# Keybon_REV_1_1.net
KiCad netlist of a schematic drawn in EAGLE
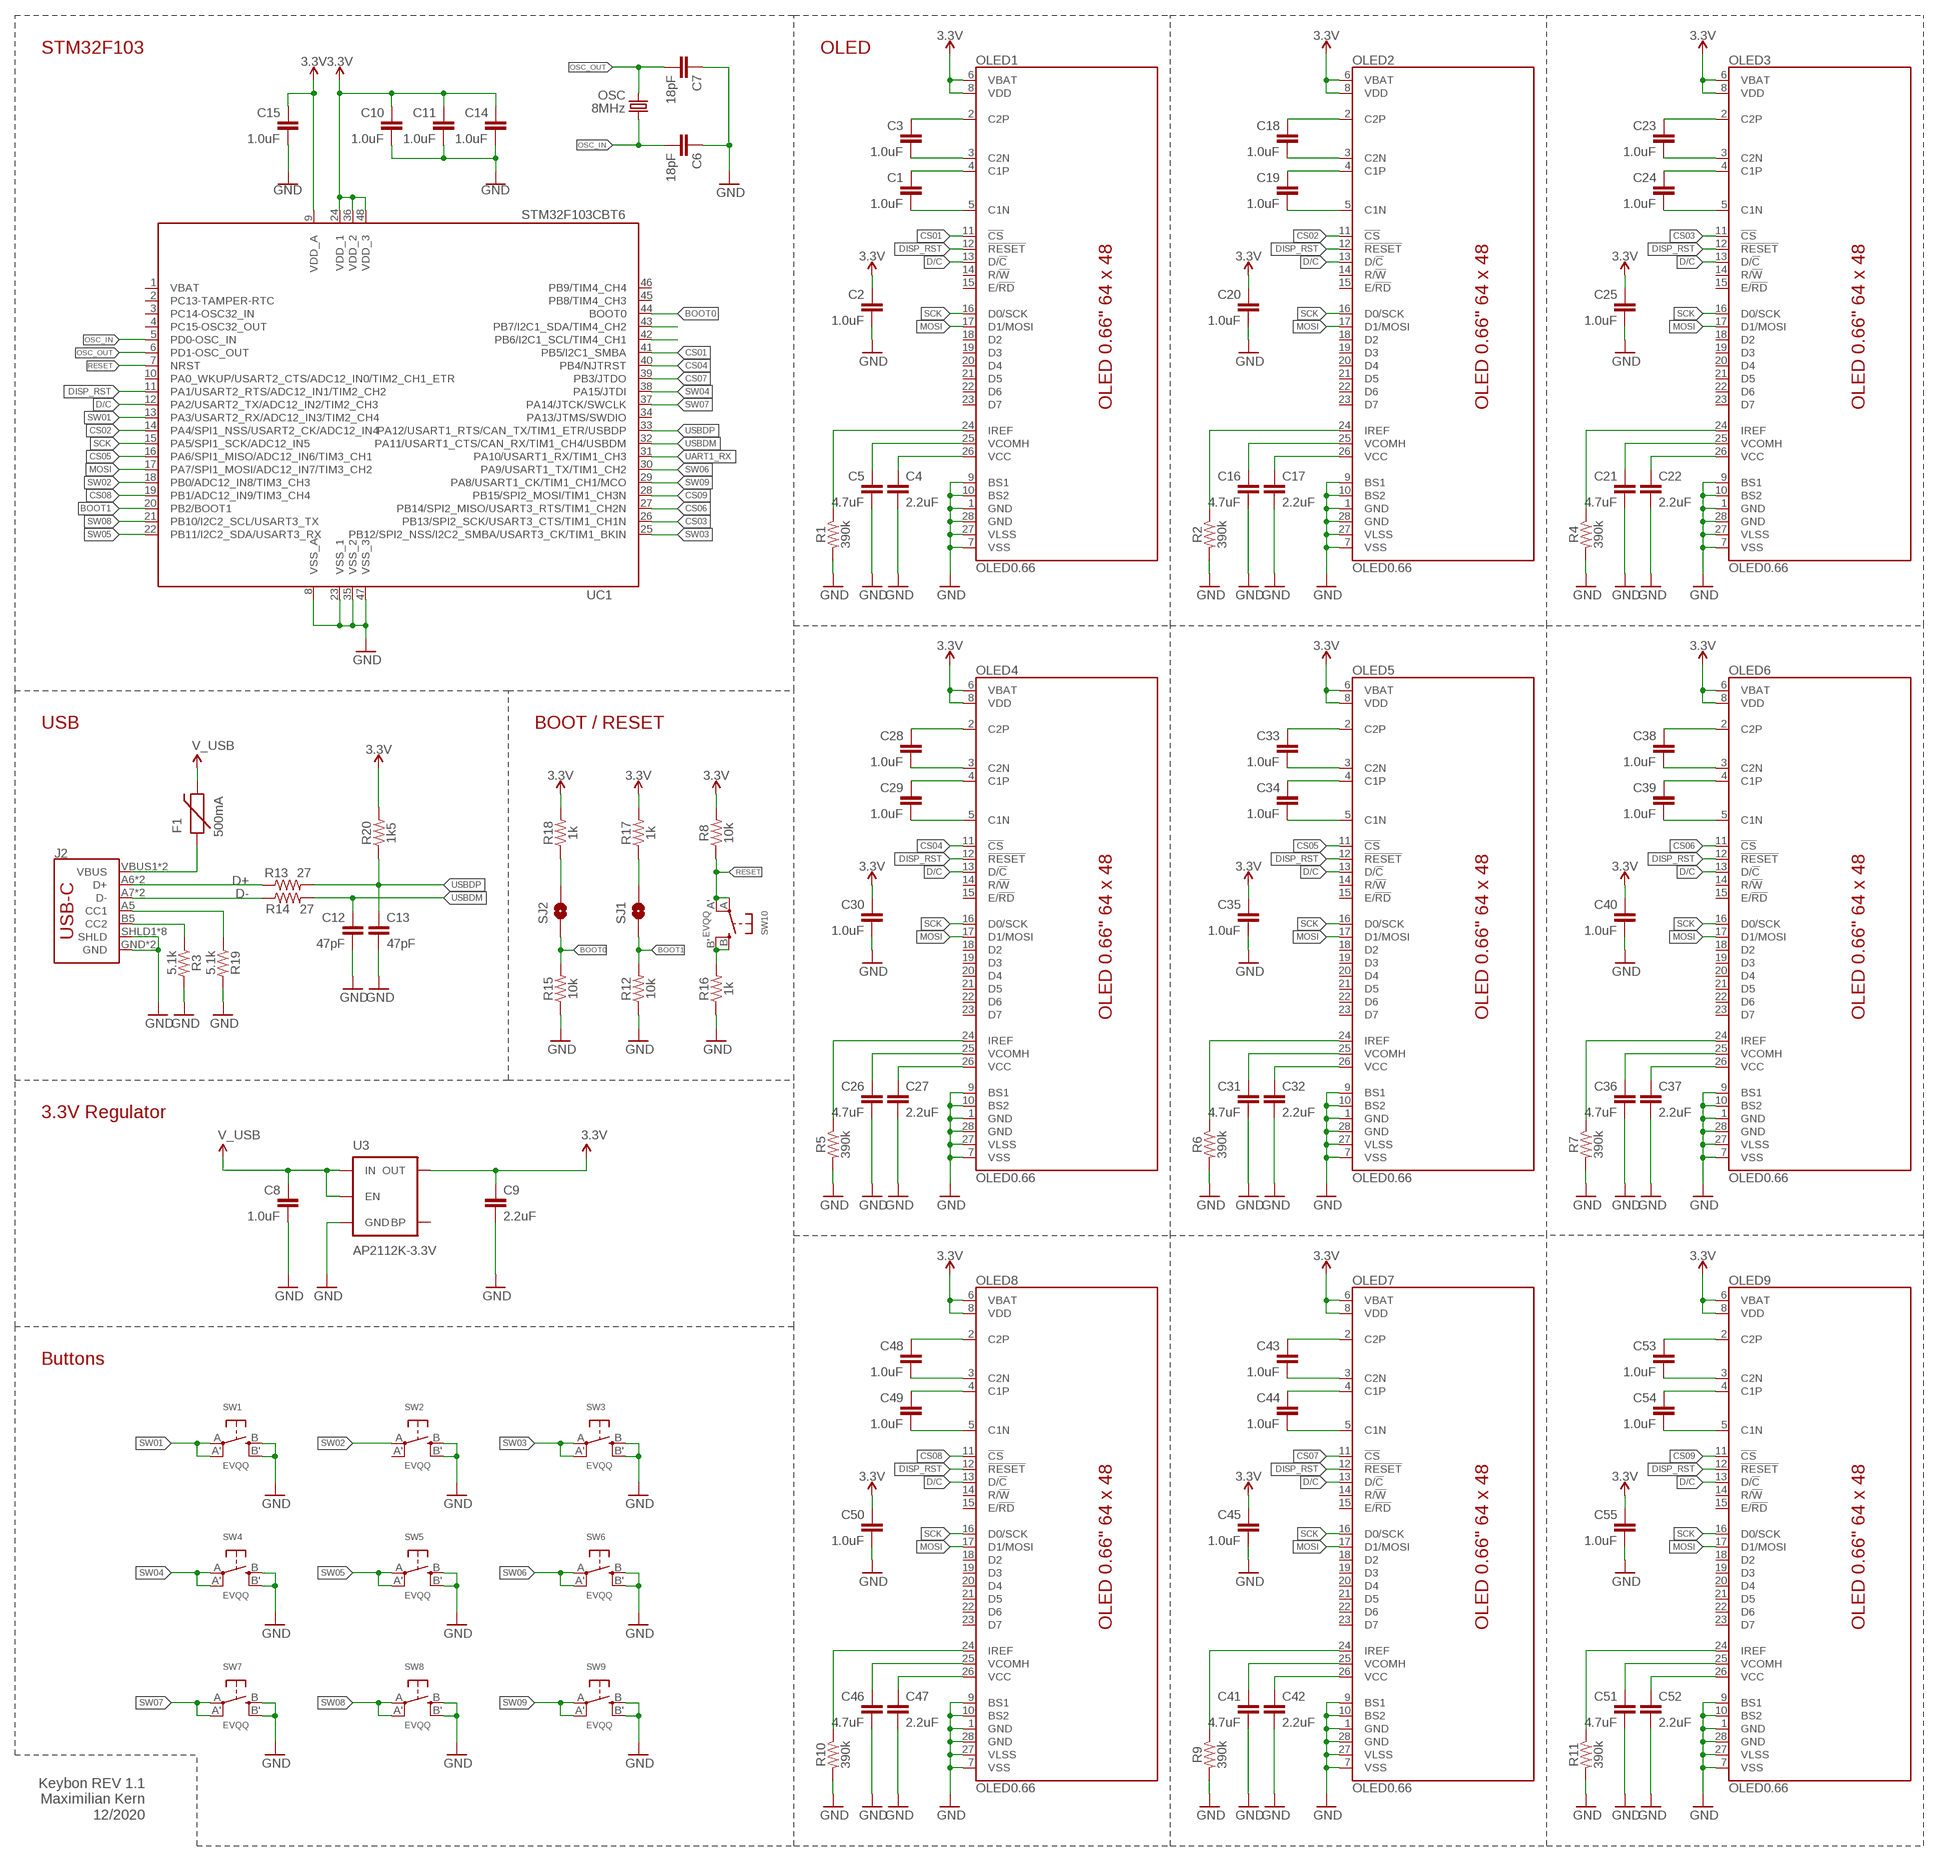
[diagram p0: schematic, sheet 1]

(export (version "E")
  (design (tool "Eeschema 10.0.6"))
  (components
    (comp (ref "C1")
      (value "1.0uF")
      (footprint "eagle-import:0805")
      (libsource (lib "eagle-import") (part "1.0UF-0805-25V-(+80/-20%)"))
    )
    (comp (ref "C2")
      (value "1.0uF")
      (footprint "eagle-import:0805")
      (libsource (lib "eagle-import") (part "1.0UF-0805-25V-(+80/-20%)"))
    )
    (comp (ref "C3")
      (value "1.0uF")
      (footprint "eagle-import:0805")
      (libsource (lib "eagle-import") (part "1.0UF-0805-25V-(+80/-20%)"))
    )
    (comp (ref "C4")
      (value "2.2uF")
      (footprint "eagle-import:0805")
      (libsource (lib "eagle-import") (part "1.0UF-0805-25V-(+80/-20%)"))
    )
    (comp (ref "C5")
      (value "4.7uF")
      (footprint "eagle-import:0603")
      (libsource (lib "eagle-import") (part "4.7UF0603"))
    )
    (comp (ref "C6")
      (value "18pF")
      (footprint "eagle-import:0603")
      (libsource (lib "eagle-import") (part "47PF-0603-50V-5%"))
    )
    (comp (ref "C7")
      (value "18pF")
      (footprint "eagle-import:0603")
      (libsource (lib "eagle-import") (part "47PF-0603-50V-5%"))
    )
    (comp (ref "C8")
      (value "1.0uF")
      (footprint "eagle-import:0805")
      (libsource (lib "eagle-import") (part "1.0UF-0805-25V-(+80/-20%)"))
    )
    (comp (ref "C9")
      (value "2.2uF")
      (footprint "eagle-import:0805")
      (libsource (lib "eagle-import") (part "1.0UF-0805-25V-(+80/-20%)"))
    )
    (comp (ref "C10")
      (value "1.0uF")
      (footprint "eagle-import:0805")
      (libsource (lib "eagle-import") (part "1.0UF-0805-25V-(+80/-20%)"))
    )
    (comp (ref "C11")
      (value "1.0uF")
      (footprint "eagle-import:0805")
      (libsource (lib "eagle-import") (part "1.0UF-0805-25V-(+80/-20%)"))
    )
    (comp (ref "C12")
      (value "47pF")
      (footprint "eagle-import:0603")
      (libsource (lib "eagle-import") (part "47PF-0603-50V-5%"))
    )
    (comp (ref "C13")
      (value "47pF")
      (footprint "eagle-import:0603")
      (libsource (lib "eagle-import") (part "47PF-0603-50V-5%"))
    )
    (comp (ref "C14")
      (value "1.0uF")
      (footprint "eagle-import:0805")
      (libsource (lib "eagle-import") (part "1.0UF-0805-25V-(+80/-20%)"))
    )
    (comp (ref "C15")
      (value "1.0uF")
      (footprint "eagle-import:0805")
      (libsource (lib "eagle-import") (part "1.0UF-0805-25V-(+80/-20%)"))
    )
    (comp (ref "C16")
      (value "4.7uF")
      (footprint "eagle-import:0603")
      (libsource (lib "eagle-import") (part "4.7UF0603"))
    )
    (comp (ref "C17")
      (value "2.2uF")
      (footprint "eagle-import:0805")
      (libsource (lib "eagle-import") (part "1.0UF-0805-25V-(+80/-20%)"))
    )
    (comp (ref "C18")
      (value "1.0uF")
      (footprint "eagle-import:0805")
      (libsource (lib "eagle-import") (part "1.0UF-0805-25V-(+80/-20%)"))
    )
    (comp (ref "C19")
      (value "1.0uF")
      (footprint "eagle-import:0805")
      (libsource (lib "eagle-import") (part "1.0UF-0805-25V-(+80/-20%)"))
    )
    (comp (ref "C20")
      (value "1.0uF")
      (footprint "eagle-import:0805")
      (libsource (lib "eagle-import") (part "1.0UF-0805-25V-(+80/-20%)"))
    )
    (comp (ref "C21")
      (value "4.7uF")
      (footprint "eagle-import:0603")
      (libsource (lib "eagle-import") (part "4.7UF0603"))
    )
    (comp (ref "C22")
      (value "2.2uF")
      (footprint "eagle-import:0805")
      (libsource (lib "eagle-import") (part "1.0UF-0805-25V-(+80/-20%)"))
    )
    (comp (ref "C23")
      (value "1.0uF")
      (footprint "eagle-import:0805")
      (libsource (lib "eagle-import") (part "1.0UF-0805-25V-(+80/-20%)"))
    )
    (comp (ref "C24")
      (value "1.0uF")
      (footprint "eagle-import:0805")
      (libsource (lib "eagle-import") (part "1.0UF-0805-25V-(+80/-20%)"))
    )
    (comp (ref "C25")
      (value "1.0uF")
      (footprint "eagle-import:0805")
      (libsource (lib "eagle-import") (part "1.0UF-0805-25V-(+80/-20%)"))
    )
    (comp (ref "C26")
      (value "4.7uF")
      (footprint "eagle-import:0603")
      (libsource (lib "eagle-import") (part "4.7UF0603"))
    )
    (comp (ref "C27")
      (value "2.2uF")
      (footprint "eagle-import:0805")
      (libsource (lib "eagle-import") (part "1.0UF-0805-25V-(+80/-20%)"))
    )
    (comp (ref "C28")
      (value "1.0uF")
      (footprint "eagle-import:0805")
      (libsource (lib "eagle-import") (part "1.0UF-0805-25V-(+80/-20%)"))
    )
    (comp (ref "C29")
      (value "1.0uF")
      (footprint "eagle-import:0805")
      (libsource (lib "eagle-import") (part "1.0UF-0805-25V-(+80/-20%)"))
    )
    (comp (ref "C30")
      (value "1.0uF")
      (footprint "eagle-import:0805")
      (libsource (lib "eagle-import") (part "1.0UF-0805-25V-(+80/-20%)"))
    )
    (comp (ref "C31")
      (value "4.7uF")
      (footprint "eagle-import:0603")
      (libsource (lib "eagle-import") (part "4.7UF0603"))
    )
    (comp (ref "C32")
      (value "2.2uF")
      (footprint "eagle-import:0805")
      (libsource (lib "eagle-import") (part "1.0UF-0805-25V-(+80/-20%)"))
    )
    (comp (ref "C33")
      (value "1.0uF")
      (footprint "eagle-import:0805")
      (libsource (lib "eagle-import") (part "1.0UF-0805-25V-(+80/-20%)"))
    )
    (comp (ref "C34")
      (value "1.0uF")
      (footprint "eagle-import:0805")
      (libsource (lib "eagle-import") (part "1.0UF-0805-25V-(+80/-20%)"))
    )
    (comp (ref "C35")
      (value "1.0uF")
      (footprint "eagle-import:0805")
      (libsource (lib "eagle-import") (part "1.0UF-0805-25V-(+80/-20%)"))
    )
    (comp (ref "C36")
      (value "4.7uF")
      (footprint "eagle-import:0603")
      (libsource (lib "eagle-import") (part "4.7UF0603"))
    )
    (comp (ref "C37")
      (value "2.2uF")
      (footprint "eagle-import:0805")
      (libsource (lib "eagle-import") (part "1.0UF-0805-25V-(+80/-20%)"))
    )
    (comp (ref "C38")
      (value "1.0uF")
      (footprint "eagle-import:0805")
      (libsource (lib "eagle-import") (part "1.0UF-0805-25V-(+80/-20%)"))
    )
    (comp (ref "C39")
      (value "1.0uF")
      (footprint "eagle-import:0805")
      (libsource (lib "eagle-import") (part "1.0UF-0805-25V-(+80/-20%)"))
    )
    (comp (ref "C40")
      (value "1.0uF")
      (footprint "eagle-import:0805")
      (libsource (lib "eagle-import") (part "1.0UF-0805-25V-(+80/-20%)"))
    )
    (comp (ref "C41")
      (value "4.7uF")
      (footprint "eagle-import:0603")
      (libsource (lib "eagle-import") (part "4.7UF0603"))
    )
    (comp (ref "C42")
      (value "2.2uF")
      (footprint "eagle-import:0805")
      (libsource (lib "eagle-import") (part "1.0UF-0805-25V-(+80/-20%)"))
    )
    (comp (ref "C43")
      (value "1.0uF")
      (footprint "eagle-import:0805")
      (libsource (lib "eagle-import") (part "1.0UF-0805-25V-(+80/-20%)"))
    )
    (comp (ref "C44")
      (value "1.0uF")
      (footprint "eagle-import:0805")
      (libsource (lib "eagle-import") (part "1.0UF-0805-25V-(+80/-20%)"))
    )
    (comp (ref "C45")
      (value "1.0uF")
      (footprint "eagle-import:0805")
      (libsource (lib "eagle-import") (part "1.0UF-0805-25V-(+80/-20%)"))
    )
    (comp (ref "C46")
      (value "4.7uF")
      (footprint "eagle-import:0603")
      (libsource (lib "eagle-import") (part "4.7UF0603"))
    )
    (comp (ref "C47")
      (value "2.2uF")
      (footprint "eagle-import:0805")
      (libsource (lib "eagle-import") (part "1.0UF-0805-25V-(+80/-20%)"))
    )
    (comp (ref "C48")
      (value "1.0uF")
      (footprint "eagle-import:0805")
      (libsource (lib "eagle-import") (part "1.0UF-0805-25V-(+80/-20%)"))
    )
    (comp (ref "C49")
      (value "1.0uF")
      (footprint "eagle-import:0805")
      (libsource (lib "eagle-import") (part "1.0UF-0805-25V-(+80/-20%)"))
    )
    (comp (ref "C50")
      (value "1.0uF")
      (footprint "eagle-import:0805")
      (libsource (lib "eagle-import") (part "1.0UF-0805-25V-(+80/-20%)"))
    )
    (comp (ref "C51")
      (value "4.7uF")
      (footprint "eagle-import:0603")
      (libsource (lib "eagle-import") (part "4.7UF0603"))
    )
    (comp (ref "C52")
      (value "2.2uF")
      (footprint "eagle-import:0805")
      (libsource (lib "eagle-import") (part "1.0UF-0805-25V-(+80/-20%)"))
    )
    (comp (ref "C53")
      (value "1.0uF")
      (footprint "eagle-import:0805")
      (libsource (lib "eagle-import") (part "1.0UF-0805-25V-(+80/-20%)"))
    )
    (comp (ref "C54")
      (value "1.0uF")
      (footprint "eagle-import:0805")
      (libsource (lib "eagle-import") (part "1.0UF-0805-25V-(+80/-20%)"))
    )
    (comp (ref "C55")
      (value "1.0uF")
      (footprint "eagle-import:0805")
      (libsource (lib "eagle-import") (part "1.0UF-0805-25V-(+80/-20%)"))
    )
    (comp (ref "F1")
      (value "500mA")
      (footprint "eagle-import:PTC-1206")
      (libsource (lib "eagle-import") (part "PTCSMD"))
    )
    (comp (ref "J2")
      (value "USB_C16PIN")
      (footprint "eagle-import:USB-C-16P")
      (libsource (lib "eagle-import") (part "USB_C16PIN"))
    )
    (comp (ref "OLED1")
      (value "OLED0.66")
      (footprint "eagle-import:OLED-0.66-64X48")
      (libsource (lib "eagle-import") (part "OLED0.66"))
    )
    (comp (ref "OLED2")
      (value "OLED0.66")
      (footprint "eagle-import:OLED-0.66-64X48")
      (libsource (lib "eagle-import") (part "OLED0.66"))
    )
    (comp (ref "OLED3")
      (value "OLED0.66")
      (footprint "eagle-import:OLED-0.66-64X48")
      (libsource (lib "eagle-import") (part "OLED0.66"))
    )
    (comp (ref "OLED4")
      (value "OLED0.66")
      (footprint "eagle-import:OLED-0.66-64X48")
      (libsource (lib "eagle-import") (part "OLED0.66"))
    )
    (comp (ref "OLED5")
      (value "OLED0.66")
      (footprint "eagle-import:OLED-0.66-64X48")
      (libsource (lib "eagle-import") (part "OLED0.66"))
    )
    (comp (ref "OLED6")
      (value "OLED0.66")
      (footprint "eagle-import:OLED-0.66-64X48")
      (libsource (lib "eagle-import") (part "OLED0.66"))
    )
    (comp (ref "OLED7")
      (value "OLED0.66")
      (footprint "eagle-import:OLED-0.66-64X48")
      (libsource (lib "eagle-import") (part "OLED0.66"))
    )
    (comp (ref "OLED8")
      (value "OLED0.66")
      (footprint "eagle-import:OLED-0.66-64X48")
      (libsource (lib "eagle-import") (part "OLED0.66"))
    )
    (comp (ref "OLED9")
      (value "OLED0.66")
      (footprint "eagle-import:OLED-0.66-64X48")
      (libsource (lib "eagle-import") (part "OLED0.66"))
    )
    (comp (ref "OSC")
      (value "8MHz")
      (footprint "eagle-import:CRYSTAL-SMD-5X3")
      (libsource (lib "eagle-import") (part "CRYSTAL5X3"))
    )
    (comp (ref "R1")
      (value "390k")
      (footprint "eagle-import:0603")
      (libsource (lib "eagle-import") (part "10KOHM-0603-1/10W-1%"))
    )
    (comp (ref "R2")
      (value "390k")
      (footprint "eagle-import:0603")
      (libsource (lib "eagle-import") (part "10KOHM-0603-1/10W-1%"))
    )
    (comp (ref "R3")
      (value "5.1k")
      (footprint "eagle-import:0603")
      (libsource (lib "eagle-import") (part "10KOHM-0603-1/10W-1%"))
    )
    (comp (ref "R4")
      (value "390k")
      (footprint "eagle-import:0603")
      (libsource (lib "eagle-import") (part "10KOHM-0603-1/10W-1%"))
    )
    (comp (ref "R5")
      (value "390k")
      (footprint "eagle-import:0603")
      (libsource (lib "eagle-import") (part "10KOHM-0603-1/10W-1%"))
    )
    (comp (ref "R6")
      (value "390k")
      (footprint "eagle-import:0603")
      (libsource (lib "eagle-import") (part "10KOHM-0603-1/10W-1%"))
    )
    (comp (ref "R7")
      (value "390k")
      (footprint "eagle-import:0603")
      (libsource (lib "eagle-import") (part "10KOHM-0603-1/10W-1%"))
    )
    (comp (ref "R8")
      (value "10k")
      (footprint "eagle-import:0603")
      (libsource (lib "eagle-import") (part "10KOHM-0603-1/10W-1%"))
    )
    (comp (ref "R9")
      (value "390k")
      (footprint "eagle-import:0603")
      (libsource (lib "eagle-import") (part "10KOHM-0603-1/10W-1%"))
    )
    (comp (ref "R10")
      (value "390k")
      (footprint "eagle-import:0603")
      (libsource (lib "eagle-import") (part "10KOHM-0603-1/10W-1%"))
    )
    (comp (ref "R11")
      (value "390k")
      (footprint "eagle-import:0603")
      (libsource (lib "eagle-import") (part "10KOHM-0603-1/10W-1%"))
    )
    (comp (ref "R12")
      (value "10k")
      (footprint "eagle-import:0603")
      (libsource (lib "eagle-import") (part "10KOHM-0603-1/10W-1%"))
    )
    (comp (ref "R13")
      (value "27")
      (footprint "eagle-import:0603")
      (libsource (lib "eagle-import") (part "27OHM1/10W1%(0603)0603-RES"))
    )
    (comp (ref "R14")
      (value "27")
      (footprint "eagle-import:0603")
      (libsource (lib "eagle-import") (part "27OHM1/10W1%(0603)0603-RES"))
    )
    (comp (ref "R15")
      (value "10k")
      (footprint "eagle-import:0603")
      (libsource (lib "eagle-import") (part "10KOHM-0603-1/10W-1%"))
    )
    (comp (ref "R16")
      (value "1k")
      (footprint "eagle-import:0603")
      (libsource (lib "eagle-import") (part "10KOHM-0603-1/10W-1%"))
    )
    (comp (ref "R17")
      (value "1k")
      (footprint "eagle-import:0603")
      (libsource (lib "eagle-import") (part "10KOHM-0603-1/10W-1%"))
    )
    (comp (ref "R18")
      (value "1k")
      (footprint "eagle-import:0603")
      (libsource (lib "eagle-import") (part "10KOHM-0603-1/10W-1%"))
    )
    (comp (ref "R19")
      (value "5.1k")
      (footprint "eagle-import:0603")
      (libsource (lib "eagle-import") (part "10KOHM-0603-1/10W-1%"))
    )
    (comp (ref "R20")
      (value "1k5")
      (footprint "eagle-import:0603")
      (libsource (lib "eagle-import") (part "10KOHM-0603-1/10W-1%"))
    )
    (comp (ref "SJ1")
      (value "JUMPER-PAD-2-NOYES_SILK")
      (footprint "eagle-import:PAD-JUMPER-2-NO_YES_SILK")
      (libsource (lib "eagle-import") (part "JUMPER-PAD-2-NOYES_SILK"))
    )
    (comp (ref "SJ2")
      (value "JUMPER-PAD-2-NOYES_SILK")
      (footprint "eagle-import:PAD-JUMPER-2-NO_YES_SILK")
      (libsource (lib "eagle-import") (part "JUMPER-PAD-2-NOYES_SILK"))
    )
    (comp (ref "SW1")
      (value "EVQQ")
      (footprint "eagle-import:EVQ-Q2_SMALLER")
      (libsource (lib "eagle-import") (part "SWITCH_TACT_SMT_EVQQ2_SMALL"))
    )
    (comp (ref "SW2")
      (value "EVQQ")
      (footprint "eagle-import:EVQ-Q2_SMALLER")
      (libsource (lib "eagle-import") (part "SWITCH_TACT_SMT_EVQQ2_SMALL"))
    )
    (comp (ref "SW3")
      (value "EVQQ")
      (footprint "eagle-import:EVQ-Q2_SMALLER")
      (libsource (lib "eagle-import") (part "SWITCH_TACT_SMT_EVQQ2_SMALL"))
    )
    (comp (ref "SW4")
      (value "EVQQ")
      (footprint "eagle-import:EVQ-Q2_SMALLER")
      (libsource (lib "eagle-import") (part "SWITCH_TACT_SMT_EVQQ2_SMALL"))
    )
    (comp (ref "SW5")
      (value "EVQQ")
      (footprint "eagle-import:EVQ-Q2_SMALLER")
      (libsource (lib "eagle-import") (part "SWITCH_TACT_SMT_EVQQ2_SMALL"))
    )
    (comp (ref "SW6")
      (value "EVQQ")
      (footprint "eagle-import:EVQ-Q2_SMALLER")
      (libsource (lib "eagle-import") (part "SWITCH_TACT_SMT_EVQQ2_SMALL"))
    )
    (comp (ref "SW7")
      (value "EVQQ")
      (footprint "eagle-import:EVQ-Q2_SMALLER")
      (libsource (lib "eagle-import") (part "SWITCH_TACT_SMT_EVQQ2_SMALL"))
    )
    (comp (ref "SW8")
      (value "EVQQ")
      (footprint "eagle-import:EVQ-Q2_SMALLER")
      (libsource (lib "eagle-import") (part "SWITCH_TACT_SMT_EVQQ2_SMALL"))
    )
    (comp (ref "SW9")
      (value "EVQQ")
      (footprint "eagle-import:EVQ-Q2_SMALLER")
      (libsource (lib "eagle-import") (part "SWITCH_TACT_SMT_EVQQ2_SMALL"))
    )
    (comp (ref "SW10")
      (value "EVQQ")
      (footprint "eagle-import:EVQ-Q2_SMALLER")
      (libsource (lib "eagle-import") (part "SWITCH_TACT_SMT_EVQQ2_SMALL"))
    )
    (comp (ref "U3")
      (value "AP2112K-3.3V")
      (footprint "eagle-import:SOT23-5")
      (libsource (lib "eagle-import") (part "V_REG_LDOSMD"))
    )
    (comp (ref "UC1")
      (value "STM32F103CBT6")
      (footprint "eagle-import:LQFP48")
      (libsource (lib "eagle-import") (part "STM32F103CB"))
    )
  )
  (nets
    (net (code "1") (name "/D+") (class "Default")
      (node (ref "J2") (pin "A6") (pinfunction "D+_A6") (pintype "bidirectional"))
      (node (ref "J2") (pin "B6") (pinfunction "D+_B6") (pintype "bidirectional"))
      (node (ref "R13") (pin "1") (pinfunction "1_1") (pintype "passive"))
    )
    (net (code "2") (name "/D-") (class "Default")
      (node (ref "J2") (pin "A7") (pinfunction "D-_A7") (pintype "bidirectional"))
      (node (ref "J2") (pin "B7") (pinfunction "D-_B7") (pintype "bidirectional"))
      (node (ref "R14") (pin "1") (pinfunction "1_1") (pintype "passive"))
    )
    (net (code "3") (name "/VBAT") (class "Default")
      (node (ref "UC1") (pin "1") (pinfunction "VBAT_1") (pintype "power_in"))
    )
    (net (code "4") (name "3.3V") (class "Default")
      (node (ref "C10") (pin "1") (pinfunction "1_1") (pintype "passive"))
      (node (ref "C11") (pin "1") (pinfunction "1_1") (pintype "passive"))
      (node (ref "C14") (pin "1") (pinfunction "1_1") (pintype "passive"))
      (node (ref "C15") (pin "1") (pinfunction "1_1") (pintype "passive"))
      (node (ref "C2") (pin "1") (pinfunction "1_1") (pintype "passive"))
      (node (ref "C20") (pin "1") (pinfunction "1_1") (pintype "passive"))
      (node (ref "C25") (pin "1") (pinfunction "1_1") (pintype "passive"))
      (node (ref "C30") (pin "1") (pinfunction "1_1") (pintype "passive"))
      (node (ref "C35") (pin "1") (pinfunction "1_1") (pintype "passive"))
      (node (ref "C40") (pin "1") (pinfunction "1_1") (pintype "passive"))
      (node (ref "C45") (pin "1") (pinfunction "1_1") (pintype "passive"))
      (node (ref "C50") (pin "1") (pinfunction "1_1") (pintype "passive"))
      (node (ref "C55") (pin "1") (pinfunction "1_1") (pintype "passive"))
      (node (ref "C9") (pin "1") (pinfunction "1_1") (pintype "passive"))
      (node (ref "OLED1") (pin "6") (pinfunction "VBAT_6") (pintype "bidirectional"))
      (node (ref "OLED1") (pin "8") (pinfunction "VDD_8") (pintype "bidirectional"))
      (node (ref "OLED2") (pin "6") (pinfunction "VBAT_6") (pintype "bidirectional"))
      (node (ref "OLED2") (pin "8") (pinfunction "VDD_8") (pintype "bidirectional"))
      (node (ref "OLED3") (pin "6") (pinfunction "VBAT_6") (pintype "bidirectional"))
      (node (ref "OLED3") (pin "8") (pinfunction "VDD_8") (pintype "bidirectional"))
      (node (ref "OLED4") (pin "6") (pinfunction "VBAT_6") (pintype "bidirectional"))
      (node (ref "OLED4") (pin "8") (pinfunction "VDD_8") (pintype "bidirectional"))
      (node (ref "OLED5") (pin "6") (pinfunction "VBAT_6") (pintype "bidirectional"))
      (node (ref "OLED5") (pin "8") (pinfunction "VDD_8") (pintype "bidirectional"))
      (node (ref "OLED6") (pin "6") (pinfunction "VBAT_6") (pintype "bidirectional"))
      (node (ref "OLED6") (pin "8") (pinfunction "VDD_8") (pintype "bidirectional"))
      (node (ref "OLED7") (pin "6") (pinfunction "VBAT_6") (pintype "bidirectional"))
      (node (ref "OLED7") (pin "8") (pinfunction "VDD_8") (pintype "bidirectional"))
      (node (ref "OLED8") (pin "6") (pinfunction "VBAT_6") (pintype "bidirectional"))
      (node (ref "OLED8") (pin "8") (pinfunction "VDD_8") (pintype "bidirectional"))
      (node (ref "OLED9") (pin "6") (pinfunction "VBAT_6") (pintype "bidirectional"))
      (node (ref "OLED9") (pin "8") (pinfunction "VDD_8") (pintype "bidirectional"))
      (node (ref "R17") (pin "2") (pinfunction "2_2") (pintype "passive"))
      (node (ref "R18") (pin "2") (pinfunction "2_2") (pintype "passive"))
      (node (ref "R20") (pin "2") (pinfunction "2_2") (pintype "passive"))
      (node (ref "R8") (pin "2") (pinfunction "2_2") (pintype "passive"))
      (node (ref "U3") (pin "5") (pinfunction "OUT_5") (pintype "passive"))
      (node (ref "UC1") (pin "24") (pinfunction "VDD_1_24") (pintype "power_in"))
      (node (ref "UC1") (pin "36") (pinfunction "VDD_2_36") (pintype "power_in"))
      (node (ref "UC1") (pin "48") (pinfunction "VDD_3_48") (pintype "power_in"))
      (node (ref "UC1") (pin "9") (pinfunction "VDD_A_9") (pintype "power_in"))
    )
    (net (code "5") (name "BOOT0") (class "Default")
      (node (ref "R15") (pin "2") (pinfunction "2_2") (pintype "passive"))
      (node (ref "SJ2") (pin "1") (pinfunction "1_1") (pintype "passive"))
      (node (ref "UC1") (pin "44") (pinfunction "BOOT0_44") (pintype "input"))
    )
    (net (code "6") (name "BOOT1") (class "Default")
      (node (ref "R12") (pin "2") (pinfunction "2_2") (pintype "passive"))
      (node (ref "SJ1") (pin "1") (pinfunction "1_1") (pintype "passive"))
      (node (ref "UC1") (pin "20") (pinfunction "PB2/BOOT1_20") (pintype "bidirectional"))
    )
    (net (code "7") (name "CS01") (class "Default")
      (node (ref "OLED1") (pin "11") (pinfunction "~{CS}_11") (pintype "bidirectional"))
      (node (ref "UC1") (pin "41") (pinfunction "PB5/I2C1_SMBA_41") (pintype "input"))
    )
    (net (code "8") (name "CS02") (class "Default")
      (node (ref "OLED2") (pin "11") (pinfunction "~{CS}_11") (pintype "bidirectional"))
      (node (ref "UC1") (pin "14") (pinfunction "PA4/SPI1_NSS/USART2_CK/ADC12_IN4_14") (pintype "bidirectional"))
    )
    (net (code "9") (name "CS03") (class "Default")
      (node (ref "OLED3") (pin "11") (pinfunction "~{CS}_11") (pintype "bidirectional"))
      (node (ref "UC1") (pin "26") (pinfunction "PB13/SPI2_SCK/USART3_CTS/TIM1_CH1N_26") (pintype "input"))
    )
    (net (code "10") (name "CS04") (class "Default")
      (node (ref "OLED4") (pin "11") (pinfunction "~{CS}_11") (pintype "bidirectional"))
      (node (ref "UC1") (pin "40") (pinfunction "PB4/NJTRST_40") (pintype "bidirectional"))
    )
    (net (code "11") (name "CS05") (class "Default")
      (node (ref "OLED5") (pin "11") (pinfunction "~{CS}_11") (pintype "bidirectional"))
      (node (ref "UC1") (pin "16") (pinfunction "PA6/SPI1_MISO/ADC12_IN6/TIM3_CH1_16") (pintype "bidirectional"))
    )
    (net (code "12") (name "CS06") (class "Default")
      (node (ref "OLED6") (pin "11") (pinfunction "~{CS}_11") (pintype "bidirectional"))
      (node (ref "UC1") (pin "27") (pinfunction "PB14/SPI2_MISO/USART3_RTS/TIM1_CH2N_27") (pintype "input"))
    )
    (net (code "13") (name "CS07") (class "Default")
      (node (ref "OLED7") (pin "11") (pinfunction "~{CS}_11") (pintype "bidirectional"))
      (node (ref "UC1") (pin "39") (pinfunction "PB3/JTDO_39") (pintype "bidirectional"))
    )
    (net (code "14") (name "CS08") (class "Default")
      (node (ref "OLED8") (pin "11") (pinfunction "~{CS}_11") (pintype "bidirectional"))
      (node (ref "UC1") (pin "19") (pinfunction "PB1/ADC12_IN9/TIM3_CH4_19") (pintype "bidirectional"))
    )
    (net (code "15") (name "CS09") (class "Default")
      (node (ref "OLED9") (pin "11") (pinfunction "~{CS}_11") (pintype "bidirectional"))
      (node (ref "UC1") (pin "28") (pinfunction "PB15/SPI2_MOSI/TIM1_CH3N_28") (pintype "input"))
    )
    (net (code "16") (name "DISP_RST") (class "Default")
      (node (ref "OLED1") (pin "12") (pinfunction "~{RESET}_12") (pintype "bidirectional"))
      (node (ref "OLED2") (pin "12") (pinfunction "~{RESET}_12") (pintype "bidirectional"))
      (node (ref "OLED3") (pin "12") (pinfunction "~{RESET}_12") (pintype "bidirectional"))
      (node (ref "OLED4") (pin "12") (pinfunction "~{RESET}_12") (pintype "bidirectional"))
      (node (ref "OLED5") (pin "12") (pinfunction "~{RESET}_12") (pintype "bidirectional"))
      (node (ref "OLED6") (pin "12") (pinfunction "~{RESET}_12") (pintype "bidirectional"))
      (node (ref "OLED7") (pin "12") (pinfunction "~{RESET}_12") (pintype "bidirectional"))
      (node (ref "OLED8") (pin "12") (pinfunction "~{RESET}_12") (pintype "bidirectional"))
      (node (ref "OLED9") (pin "12") (pinfunction "~{RESET}_12") (pintype "bidirectional"))
      (node (ref "UC1") (pin "11") (pinfunction "PA1/USART2_RTS/ADC12_IN1/TIM2_CH2_11") (pintype "bidirectional"))
    )
    (net (code "17") (name "D{slash}C") (class "Default")
      (node (ref "OLED1") (pin "13") (pinfunction "D/~{C}_13") (pintype "bidirectional"))
      (node (ref "OLED2") (pin "13") (pinfunction "D/~{C}_13") (pintype "bidirectional"))
      (node (ref "OLED3") (pin "13") (pinfunction "D/~{C}_13") (pintype "bidirectional"))
      (node (ref "OLED4") (pin "13") (pinfunction "D/~{C}_13") (pintype "bidirectional"))
      (node (ref "OLED5") (pin "13") (pinfunction "D/~{C}_13") (pintype "bidirectional"))
      (node (ref "OLED6") (pin "13") (pinfunction "D/~{C}_13") (pintype "bidirectional"))
      (node (ref "OLED7") (pin "13") (pinfunction "D/~{C}_13") (pintype "bidirectional"))
      (node (ref "OLED8") (pin "13") (pinfunction "D/~{C}_13") (pintype "bidirectional"))
      (node (ref "OLED9") (pin "13") (pinfunction "D/~{C}_13") (pintype "bidirectional"))
      (node (ref "UC1") (pin "12") (pinfunction "PA2/USART2_TX/ADC12_IN2/TIM2_CH3_12") (pintype "bidirectional"))
    )
    (net (code "18") (name "GND") (class "Default")
      (node (ref "C10") (pin "2") (pinfunction "2_2") (pintype "passive"))
      (node (ref "C11") (pin "2") (pinfunction "2_2") (pintype "passive"))
      (node (ref "C12") (pin "2") (pinfunction "2_2") (pintype "passive"))
      (node (ref "C13") (pin "2") (pinfunction "2_2") (pintype "passive"))
      (node (ref "C14") (pin "2") (pinfunction "2_2") (pintype "passive"))
      (node (ref "C15") (pin "2") (pinfunction "2_2") (pintype "passive"))
      (node (ref "C16") (pin "2") (pinfunction "2_2") (pintype "passive"))
      (node (ref "C17") (pin "2") (pinfunction "2_2") (pintype "passive"))
      (node (ref "C2") (pin "2") (pinfunction "2_2") (pintype "passive"))
      (node (ref "C20") (pin "2") (pinfunction "2_2") (pintype "passive"))
      (node (ref "C21") (pin "2") (pinfunction "2_2") (pintype "passive"))
      (node (ref "C22") (pin "2") (pinfunction "2_2") (pintype "passive"))
      (node (ref "C25") (pin "2") (pinfunction "2_2") (pintype "passive"))
      (node (ref "C26") (pin "2") (pinfunction "2_2") (pintype "passive"))
      (node (ref "C27") (pin "2") (pinfunction "2_2") (pintype "passive"))
      (node (ref "C30") (pin "2") (pinfunction "2_2") (pintype "passive"))
      (node (ref "C31") (pin "2") (pinfunction "2_2") (pintype "passive"))
      (node (ref "C32") (pin "2") (pinfunction "2_2") (pintype "passive"))
      (node (ref "C35") (pin "2") (pinfunction "2_2") (pintype "passive"))
      (node (ref "C36") (pin "2") (pinfunction "2_2") (pintype "passive"))
      (node (ref "C37") (pin "2") (pinfunction "2_2") (pintype "passive"))
      (node (ref "C4") (pin "2") (pinfunction "2_2") (pintype "passive"))
      (node (ref "C40") (pin "2") (pinfunction "2_2") (pintype "passive"))
      (node (ref "C41") (pin "2") (pinfunction "2_2") (pintype "passive"))
      (node (ref "C42") (pin "2") (pinfunction "2_2") (pintype "passive"))
      (node (ref "C45") (pin "2") (pinfunction "2_2") (pintype "passive"))
      (node (ref "C46") (pin "2") (pinfunction "2_2") (pintype "passive"))
      (node (ref "C47") (pin "2") (pinfunction "2_2") (pintype "passive"))
      (node (ref "C5") (pin "2") (pinfunction "2_2") (pintype "passive"))
      (node (ref "C50") (pin "2") (pinfunction "2_2") (pintype "passive"))
      (node (ref "C51") (pin "2") (pinfunction "2_2") (pintype "passive"))
      (node (ref "C52") (pin "2") (pinfunction "2_2") (pintype "passive"))
      (node (ref "C55") (pin "2") (pinfunction "2_2") (pintype "passive"))
      (node (ref "C6") (pin "1") (pinfunction "1_1") (pintype "passive"))
      (node (ref "C7") (pin "1") (pinfunction "1_1") (pintype "passive"))
      (node (ref "C8") (pin "2") (pinfunction "2_2") (pintype "passive"))
      (node (ref "C9") (pin "2") (pinfunction "2_2") (pintype "passive"))
      (node (ref "J2") (pin "GND") (pinfunction "GND_GND") (pintype "bidirectional"))
      (node (ref "J2") (pin "GND2") (pinfunction "GND_GND2") (pintype "bidirectional"))
      (node (ref "J2") (pin "SHLD1") (pinfunction "SHLD_SHLD1") (pintype "bidirectional"))
      (node (ref "J2") (pin "SHLD2") (pinfunction "SHLD_SHLD2") (pintype "bidirectional"))
      (node (ref "J2") (pin "SHLD3") (pinfunction "SHLD_SHLD3") (pintype "bidirectional"))
      (node (ref "J2") (pin "SHLD4") (pinfunction "SHLD_SHLD4") (pintype "bidirectional"))
      (node (ref "J2") (pin "SHLD5") (pinfunction "SHLD_SHLD5") (pintype "bidirectional"))
      (node (ref "J2") (pin "SHLD6") (pinfunction "SHLD_SHLD6") (pintype "bidirectional"))
      (node (ref "J2") (pin "SHLD7") (pinfunction "SHLD_SHLD7") (pintype "bidirectional"))
      (node (ref "J2") (pin "SHLD8") (pinfunction "SHLD_SHLD8") (pintype "bidirectional"))
      (node (ref "OLED1") (pin "1") (pinfunction "GND_1") (pintype "bidirectional"))
      (node (ref "OLED1") (pin "10") (pinfunction "BS2_10") (pintype "bidirectional"))
      (node (ref "OLED1") (pin "27") (pinfunction "VLSS_27") (pintype "bidirectional"))
      (node (ref "OLED1") (pin "28") (pinfunction "GND_28") (pintype "bidirectional"))
      (node (ref "OLED1") (pin "7") (pinfunction "VSS_7") (pintype "bidirectional"))
      (node (ref "OLED1") (pin "9") (pinfunction "BS1_9") (pintype "bidirectional"))
      (node (ref "OLED2") (pin "1") (pinfunction "GND_1") (pintype "bidirectional"))
      (node (ref "OLED2") (pin "10") (pinfunction "BS2_10") (pintype "bidirectional"))
      (node (ref "OLED2") (pin "27") (pinfunction "VLSS_27") (pintype "bidirectional"))
      (node (ref "OLED2") (pin "28") (pinfunction "GND_28") (pintype "bidirectional"))
      (node (ref "OLED2") (pin "7") (pinfunction "VSS_7") (pintype "bidirectional"))
      (node (ref "OLED2") (pin "9") (pinfunction "BS1_9") (pintype "bidirectional"))
      (node (ref "OLED3") (pin "1") (pinfunction "GND_1") (pintype "bidirectional"))
      (node (ref "OLED3") (pin "10") (pinfunction "BS2_10") (pintype "bidirectional"))
      (node (ref "OLED3") (pin "27") (pinfunction "VLSS_27") (pintype "bidirectional"))
      (node (ref "OLED3") (pin "28") (pinfunction "GND_28") (pintype "bidirectional"))
      (node (ref "OLED3") (pin "7") (pinfunction "VSS_7") (pintype "bidirectional"))
      (node (ref "OLED3") (pin "9") (pinfunction "BS1_9") (pintype "bidirectional"))
      (node (ref "OLED4") (pin "1") (pinfunction "GND_1") (pintype "bidirectional"))
      (node (ref "OLED4") (pin "10") (pinfunction "BS2_10") (pintype "bidirectional"))
      (node (ref "OLED4") (pin "27") (pinfunction "VLSS_27") (pintype "bidirectional"))
      (node (ref "OLED4") (pin "28") (pinfunction "GND_28") (pintype "bidirectional"))
      (node (ref "OLED4") (pin "7") (pinfunction "VSS_7") (pintype "bidirectional"))
      (node (ref "OLED4") (pin "9") (pinfunction "BS1_9") (pintype "bidirectional"))
      (node (ref "OLED5") (pin "1") (pinfunction "GND_1") (pintype "bidirectional"))
      (node (ref "OLED5") (pin "10") (pinfunction "BS2_10") (pintype "bidirectional"))
      (node (ref "OLED5") (pin "27") (pinfunction "VLSS_27") (pintype "bidirectional"))
      (node (ref "OLED5") (pin "28") (pinfunction "GND_28") (pintype "bidirectional"))
      (node (ref "OLED5") (pin "7") (pinfunction "VSS_7") (pintype "bidirectional"))
      (node (ref "OLED5") (pin "9") (pinfunction "BS1_9") (pintype "bidirectional"))
      (node (ref "OLED6") (pin "1") (pinfunction "GND_1") (pintype "bidirectional"))
      (node (ref "OLED6") (pin "10") (pinfunction "BS2_10") (pintype "bidirectional"))
      (node (ref "OLED6") (pin "27") (pinfunction "VLSS_27") (pintype "bidirectional"))
      (node (ref "OLED6") (pin "28") (pinfunction "GND_28") (pintype "bidirectional"))
      (node (ref "OLED6") (pin "7") (pinfunction "VSS_7") (pintype "bidirectional"))
      (node (ref "OLED6") (pin "9") (pinfunction "BS1_9") (pintype "bidirectional"))
      (node (ref "OLED7") (pin "1") (pinfunction "GND_1") (pintype "bidirectional"))
      (node (ref "OLED7") (pin "10") (pinfunction "BS2_10") (pintype "bidirectional"))
      (node (ref "OLED7") (pin "27") (pinfunction "VLSS_27") (pintype "bidirectional"))
      (node (ref "OLED7") (pin "28") (pinfunction "GND_28") (pintype "bidirectional"))
      (node (ref "OLED7") (pin "7") (pinfunction "VSS_7") (pintype "bidirectional"))
      (node (ref "OLED7") (pin "9") (pinfunction "BS1_9") (pintype "bidirectional"))
      (node (ref "OLED8") (pin "1") (pinfunction "GND_1") (pintype "bidirectional"))
      (node (ref "OLED8") (pin "10") (pinfunction "BS2_10") (pintype "bidirectional"))
      (node (ref "OLED8") (pin "27") (pinfunction "VLSS_27") (pintype "bidirectional"))
      (node (ref "OLED8") (pin "28") (pinfunction "GND_28") (pintype "bidirectional"))
      (node (ref "OLED8") (pin "7") (pinfunction "VSS_7") (pintype "bidirectional"))
      (node (ref "OLED8") (pin "9") (pinfunction "BS1_9") (pintype "bidirectional"))
      (node (ref "OLED9") (pin "1") (pinfunction "GND_1") (pintype "bidirectional"))
      (node (ref "OLED9") (pin "10") (pinfunction "BS2_10") (pintype "bidirectional"))
      (node (ref "OLED9") (pin "27") (pinfunction "VLSS_27") (pintype "bidirectional"))
      (node (ref "OLED9") (pin "28") (pinfunction "GND_28") (pintype "bidirectional"))
      (node (ref "OLED9") (pin "7") (pinfunction "VSS_7") (pintype "bidirectional"))
      (node (ref "OLED9") (pin "9") (pinfunction "BS1_9") (pintype "bidirectional"))
      (node (ref "R1") (pin "2") (pinfunction "2_2") (pintype "passive"))
      (node (ref "R10") (pin "2") (pinfunction "2_2") (pintype "passive"))
      (node (ref "R11") (pin "2") (pinfunction "2_2") (pintype "passive"))
      (node (ref "R12") (pin "1") (pinfunction "1_1") (pintype "passive"))
      (node (ref "R15") (pin "1") (pinfunction "1_1") (pintype "passive"))
      (node (ref "R16") (pin "1") (pinfunction "1_1") (pintype "passive"))
      (node (ref "R19") (pin "2") (pinfunction "2_2") (pintype "passive"))
      (node (ref "R2") (pin "2") (pinfunction "2_2") (pintype "passive"))
      (node (ref "R3") (pin "2") (pinfunction "2_2") (pintype "passive"))
      (node (ref "R4") (pin "2") (pinfunction "2_2") (pintype "passive"))
      (node (ref "R5") (pin "2") (pinfunction "2_2") (pintype "passive"))
      (node (ref "R6") (pin "2") (pinfunction "2_2") (pintype "passive"))
      (node (ref "R7") (pin "2") (pinfunction "2_2") (pintype "passive"))
      (node (ref "R9") (pin "2") (pinfunction "2_2") (pintype "passive"))
      (node (ref "SW1") (pin "B") (pinfunction "S_B") (pintype "passive"))
      (node (ref "SW1") (pin "B'") (pinfunction "S1_B'") (pintype "passive"))
      (node (ref "SW2") (pin "B") (pinfunction "S_B") (pintype "passive"))
      (node (ref "SW2") (pin "B'") (pinfunction "S1_B'") (pintype "passive"))
      (node (ref "SW3") (pin "B") (pinfunction "S_B") (pintype "passive"))
      (node (ref "SW3") (pin "B'") (pinfunction "S1_B'") (pintype "passive"))
      (node (ref "SW4") (pin "B") (pinfunction "S_B") (pintype "passive"))
      (node (ref "SW4") (pin "B'") (pinfunction "S1_B'") (pintype "passive"))
      (node (ref "SW5") (pin "B") (pinfunction "S_B") (pintype "passive"))
      (node (ref "SW5") (pin "B'") (pinfunction "S1_B'") (pintype "passive"))
      (node (ref "SW6") (pin "B") (pinfunction "S_B") (pintype "passive"))
      (node (ref "SW6") (pin "B'") (pinfunction "S1_B'") (pintype "passive"))
      (node (ref "SW7") (pin "B") (pinfunction "S_B") (pintype "passive"))
      (node (ref "SW7") (pin "B'") (pinfunction "S1_B'") (pintype "passive"))
      (node (ref "SW8") (pin "B") (pinfunction "S_B") (pintype "passive"))
      (node (ref "SW8") (pin "B'") (pinfunction "S1_B'") (pintype "passive"))
      (node (ref "SW9") (pin "B") (pinfunction "S_B") (pintype "passive"))
      (node (ref "SW9") (pin "B'") (pinfunction "S1_B'") (pintype "passive"))
      (node (ref "U3") (pin "2") (pinfunction "GND_2") (pintype "input"))
      (node (ref "UC1") (pin "23") (pinfunction "VSS_1_23") (pintype "power_in"))
      (node (ref "UC1") (pin "35") (pinfunction "VSS_2_35") (pintype "power_in"))
      (node (ref "UC1") (pin "47") (pinfunction "VSS_3_47") (pintype "power_in"))
      (node (ref "UC1") (pin "8") (pinfunction "VSS_A_8") (pintype "power_in"))
    )
    (net (code "19") (name "MOSI") (class "Default")
      (node (ref "OLED1") (pin "17") (pinfunction "D1/MOSI_17") (pintype "bidirectional"))
      (node (ref "OLED2") (pin "17") (pinfunction "D1/MOSI_17") (pintype "bidirectional"))
      (node (ref "OLED3") (pin "17") (pinfunction "D1/MOSI_17") (pintype "bidirectional"))
      (node (ref "OLED4") (pin "17") (pinfunction "D1/MOSI_17") (pintype "bidirectional"))
      (node (ref "OLED5") (pin "17") (pinfunction "D1/MOSI_17") (pintype "bidirectional"))
      (node (ref "OLED6") (pin "17") (pinfunction "D1/MOSI_17") (pintype "bidirectional"))
      (node (ref "OLED7") (pin "17") (pinfunction "D1/MOSI_17") (pintype "bidirectional"))
      (node (ref "OLED8") (pin "17") (pinfunction "D1/MOSI_17") (pintype "bidirectional"))
      (node (ref "OLED9") (pin "17") (pinfunction "D1/MOSI_17") (pintype "bidirectional"))
      (node (ref "UC1") (pin "17") (pinfunction "PA7/SPI1_MOSI/ADC12_IN7/TIM3_CH2_17") (pintype "bidirectional"))
    )
    (net (code "20") (name "Net-(F1-Pad1)") (class "Default")
      (node (ref "F1") (pin "1") (pinfunction "1_1") (pintype "bidirectional"))
      (node (ref "J2") (pin "VBUS1") (pinfunction "VBUS_VBUS1") (pintype "bidirectional"))
      (node (ref "J2") (pin "VBUS2") (pinfunction "VBUS_VBUS2") (pintype "bidirectional"))
    )
    (net (code "21") (name "Net-(J2-CC1)") (class "Default")
      (node (ref "J2") (pin "A5") (pinfunction "CC1_A5") (pintype "bidirectional"))
      (node (ref "R19") (pin "1") (pinfunction "1_1") (pintype "passive"))
    )
    (net (code "22") (name "Net-(J2-CC2)") (class "Default")
      (node (ref "J2") (pin "B5") (pinfunction "CC2_B5") (pintype "bidirectional"))
      (node (ref "R3") (pin "1") (pinfunction "1_1") (pintype "passive"))
    )
    (net (code "23") (name "Net-(OLED1-C1N)") (class "Default")
      (node (ref "C1") (pin "2") (pinfunction "2_2") (pintype "passive"))
      (node (ref "OLED1") (pin "5") (pinfunction "C1N_5") (pintype "bidirectional"))
    )
    (net (code "24") (name "Net-(OLED1-C1P)") (class "Default")
      (node (ref "C1") (pin "1") (pinfunction "1_1") (pintype "passive"))
      (node (ref "OLED1") (pin "4") (pinfunction "C1P_4") (pintype "bidirectional"))
    )
    (net (code "25") (name "Net-(OLED1-C2N)") (class "Default")
      (node (ref "C3") (pin "2") (pinfunction "2_2") (pintype "passive"))
      (node (ref "OLED1") (pin "3") (pinfunction "C2N_3") (pintype "bidirectional"))
    )
    (net (code "26") (name "Net-(OLED1-C2P)") (class "Default")
      (node (ref "C3") (pin "1") (pinfunction "1_1") (pintype "passive"))
      (node (ref "OLED1") (pin "2") (pinfunction "C2P_2") (pintype "bidirectional"))
    )
    (net (code "27") (name "Net-(OLED1-IREF)") (class "Default")
      (node (ref "OLED1") (pin "24") (pinfunction "IREF_24") (pintype "bidirectional"))
      (node (ref "R1") (pin "1") (pinfunction "1_1") (pintype "passive"))
    )
    (net (code "28") (name "Net-(OLED1-VCC)") (class "Default")
      (node (ref "C4") (pin "1") (pinfunction "1_1") (pintype "passive"))
      (node (ref "OLED1") (pin "26") (pinfunction "VCC_26") (pintype "bidirectional"))
    )
    (net (code "29") (name "Net-(OLED1-VCOMH)") (class "Default")
      (node (ref "C5") (pin "1") (pinfunction "1_1") (pintype "passive"))
      (node (ref "OLED1") (pin "25") (pinfunction "VCOMH_25") (pintype "bidirectional"))
    )
    (net (code "30") (name "Net-(OLED2-C1N)") (class "Default")
      (node (ref "C19") (pin "2") (pinfunction "2_2") (pintype "passive"))
      (node (ref "OLED2") (pin "5") (pinfunction "C1N_5") (pintype "bidirectional"))
    )
    (net (code "31") (name "Net-(OLED2-C1P)") (class "Default")
      (node (ref "C19") (pin "1") (pinfunction "1_1") (pintype "passive"))
      (node (ref "OLED2") (pin "4") (pinfunction "C1P_4") (pintype "bidirectional"))
    )
    (net (code "32") (name "Net-(OLED2-C2N)") (class "Default")
      (node (ref "C18") (pin "2") (pinfunction "2_2") (pintype "passive"))
      (node (ref "OLED2") (pin "3") (pinfunction "C2N_3") (pintype "bidirectional"))
    )
    (net (code "33") (name "Net-(OLED2-C2P)") (class "Default")
      (node (ref "C18") (pin "1") (pinfunction "1_1") (pintype "passive"))
      (node (ref "OLED2") (pin "2") (pinfunction "C2P_2") (pintype "bidirectional"))
    )
    (net (code "34") (name "Net-(OLED2-IREF)") (class "Default")
      (node (ref "OLED2") (pin "24") (pinfunction "IREF_24") (pintype "bidirectional"))
      (node (ref "R2") (pin "1") (pinfunction "1_1") (pintype "passive"))
    )
    (net (code "35") (name "Net-(OLED2-VCC)") (class "Default")
      (node (ref "C17") (pin "1") (pinfunction "1_1") (pintype "passive"))
      (node (ref "OLED2") (pin "26") (pinfunction "VCC_26") (pintype "bidirectional"))
    )
    (net (code "36") (name "Net-(OLED2-VCOMH)") (class "Default")
      (node (ref "C16") (pin "1") (pinfunction "1_1") (pintype "passive"))
      (node (ref "OLED2") (pin "25") (pinfunction "VCOMH_25") (pintype "bidirectional"))
    )
    (net (code "37") (name "Net-(OLED3-C1N)") (class "Default")
      (node (ref "C24") (pin "2") (pinfunction "2_2") (pintype "passive"))
      (node (ref "OLED3") (pin "5") (pinfunction "C1N_5") (pintype "bidirectional"))
    )
    (net (code "38") (name "Net-(OLED3-C1P)") (class "Default")
      (node (ref "C24") (pin "1") (pinfunction "1_1") (pintype "passive"))
      (node (ref "OLED3") (pin "4") (pinfunction "C1P_4") (pintype "bidirectional"))
    )
    (net (code "39") (name "Net-(OLED3-C2N)") (class "Default")
      (node (ref "C23") (pin "2") (pinfunction "2_2") (pintype "passive"))
      (node (ref "OLED3") (pin "3") (pinfunction "C2N_3") (pintype "bidirectional"))
    )
    (net (code "40") (name "Net-(OLED3-C2P)") (class "Default")
      (node (ref "C23") (pin "1") (pinfunction "1_1") (pintype "passive"))
      (node (ref "OLED3") (pin "2") (pinfunction "C2P_2") (pintype "bidirectional"))
    )
    (net (code "41") (name "Net-(OLED3-IREF)") (class "Default")
      (node (ref "OLED3") (pin "24") (pinfunction "IREF_24") (pintype "bidirectional"))
      (node (ref "R4") (pin "1") (pinfunction "1_1") (pintype "passive"))
    )
    (net (code "42") (name "Net-(OLED3-VCC)") (class "Default")
      (node (ref "C22") (pin "1") (pinfunction "1_1") (pintype "passive"))
      (node (ref "OLED3") (pin "26") (pinfunction "VCC_26") (pintype "bidirectional"))
    )
    (net (code "43") (name "Net-(OLED3-VCOMH)") (class "Default")
      (node (ref "C21") (pin "1") (pinfunction "1_1") (pintype "passive"))
      (node (ref "OLED3") (pin "25") (pinfunction "VCOMH_25") (pintype "bidirectional"))
    )
    (net (code "44") (name "Net-(OLED4-C1N)") (class "Default")
      (node (ref "C29") (pin "2") (pinfunction "2_2") (pintype "passive"))
      (node (ref "OLED4") (pin "5") (pinfunction "C1N_5") (pintype "bidirectional"))
    )
    (net (code "45") (name "Net-(OLED4-C1P)") (class "Default")
      (node (ref "C29") (pin "1") (pinfunction "1_1") (pintype "passive"))
      (node (ref "OLED4") (pin "4") (pinfunction "C1P_4") (pintype "bidirectional"))
    )
    (net (code "46") (name "Net-(OLED4-C2N)") (class "Default")
      (node (ref "C28") (pin "2") (pinfunction "2_2") (pintype "passive"))
      (node (ref "OLED4") (pin "3") (pinfunction "C2N_3") (pintype "bidirectional"))
    )
    (net (code "47") (name "Net-(OLED4-C2P)") (class "Default")
      (node (ref "C28") (pin "1") (pinfunction "1_1") (pintype "passive"))
      (node (ref "OLED4") (pin "2") (pinfunction "C2P_2") (pintype "bidirectional"))
    )
    (net (code "48") (name "Net-(OLED4-IREF)") (class "Default")
      (node (ref "OLED4") (pin "24") (pinfunction "IREF_24") (pintype "bidirectional"))
      (node (ref "R5") (pin "1") (pinfunction "1_1") (pintype "passive"))
    )
    (net (code "49") (name "Net-(OLED4-VCC)") (class "Default")
      (node (ref "C27") (pin "1") (pinfunction "1_1") (pintype "passive"))
      (node (ref "OLED4") (pin "26") (pinfunction "VCC_26") (pintype "bidirectional"))
    )
    (net (code "50") (name "Net-(OLED4-VCOMH)") (class "Default")
      (node (ref "C26") (pin "1") (pinfunction "1_1") (pintype "passive"))
      (node (ref "OLED4") (pin "25") (pinfunction "VCOMH_25") (pintype "bidirectional"))
    )
    (net (code "51") (name "Net-(OLED5-C1N)") (class "Default")
      (node (ref "C34") (pin "2") (pinfunction "2_2") (pintype "passive"))
      (node (ref "OLED5") (pin "5") (pinfunction "C1N_5") (pintype "bidirectional"))
    )
    (net (code "52") (name "Net-(OLED5-C1P)") (class "Default")
      (node (ref "C34") (pin "1") (pinfunction "1_1") (pintype "passive"))
      (node (ref "OLED5") (pin "4") (pinfunction "C1P_4") (pintype "bidirectional"))
    )
    (net (code "53") (name "Net-(OLED5-C2N)") (class "Default")
      (node (ref "C33") (pin "2") (pinfunction "2_2") (pintype "passive"))
      (node (ref "OLED5") (pin "3") (pinfunction "C2N_3") (pintype "bidirectional"))
    )
    (net (code "54") (name "Net-(OLED5-C2P)") (class "Default")
      (node (ref "C33") (pin "1") (pinfunction "1_1") (pintype "passive"))
      (node (ref "OLED5") (pin "2") (pinfunction "C2P_2") (pintype "bidirectional"))
    )
    (net (code "55") (name "Net-(OLED5-IREF)") (class "Default")
      (node (ref "OLED5") (pin "24") (pinfunction "IREF_24") (pintype "bidirectional"))
      (node (ref "R6") (pin "1") (pinfunction "1_1") (pintype "passive"))
    )
    (net (code "56") (name "Net-(OLED5-VCC)") (class "Default")
      (node (ref "C32") (pin "1") (pinfunction "1_1") (pintype "passive"))
      (node (ref "OLED5") (pin "26") (pinfunction "VCC_26") (pintype "bidirectional"))
    )
    (net (code "57") (name "Net-(OLED5-VCOMH)") (class "Default")
      (node (ref "C31") (pin "1") (pinfunction "1_1") (pintype "passive"))
      (node (ref "OLED5") (pin "25") (pinfunction "VCOMH_25") (pintype "bidirectional"))
    )
    (net (code "58") (name "Net-(OLED6-C1N)") (class "Default")
      (node (ref "C39") (pin "2") (pinfunction "2_2") (pintype "passive"))
      (node (ref "OLED6") (pin "5") (pinfunction "C1N_5") (pintype "bidirectional"))
    )
    (net (code "59") (name "Net-(OLED6-C1P)") (class "Default")
      (node (ref "C39") (pin "1") (pinfunction "1_1") (pintype "passive"))
      (node (ref "OLED6") (pin "4") (pinfunction "C1P_4") (pintype "bidirectional"))
    )
    (net (code "60") (name "Net-(OLED6-C2N)") (class "Default")
      (node (ref "C38") (pin "2") (pinfunction "2_2") (pintype "passive"))
      (node (ref "OLED6") (pin "3") (pinfunction "C2N_3") (pintype "bidirectional"))
    )
    (net (code "61") (name "Net-(OLED6-C2P)") (class "Default")
      (node (ref "C38") (pin "1") (pinfunction "1_1") (pintype "passive"))
      (node (ref "OLED6") (pin "2") (pinfunction "C2P_2") (pintype "bidirectional"))
    )
    (net (code "62") (name "Net-(OLED6-IREF)") (class "Default")
      (node (ref "OLED6") (pin "24") (pinfunction "IREF_24") (pintype "bidirectional"))
      (node (ref "R7") (pin "1") (pinfunction "1_1") (pintype "passive"))
    )
    (net (code "63") (name "Net-(OLED6-VCC)") (class "Default")
      (node (ref "C37") (pin "1") (pinfunction "1_1") (pintype "passive"))
      (node (ref "OLED6") (pin "26") (pinfunction "VCC_26") (pintype "bidirectional"))
    )
    (net (code "64") (name "Net-(OLED6-VCOMH)") (class "Default")
      (node (ref "C36") (pin "1") (pinfunction "1_1") (pintype "passive"))
      (node (ref "OLED6") (pin "25") (pinfunction "VCOMH_25") (pintype "bidirectional"))
    )
    (net (code "65") (name "Net-(OLED7-C1N)") (class "Default")
      (node (ref "C44") (pin "2") (pinfunction "2_2") (pintype "passive"))
      (node (ref "OLED7") (pin "5") (pinfunction "C1N_5") (pintype "bidirectional"))
    )
    (net (code "66") (name "Net-(OLED7-C1P)") (class "Default")
      (node (ref "C44") (pin "1") (pinfunction "1_1") (pintype "passive"))
      (node (ref "OLED7") (pin "4") (pinfunction "C1P_4") (pintype "bidirectional"))
    )
    (net (code "67") (name "Net-(OLED7-C2N)") (class "Default")
      (node (ref "C43") (pin "2") (pinfunction "2_2") (pintype "passive"))
      (node (ref "OLED7") (pin "3") (pinfunction "C2N_3") (pintype "bidirectional"))
    )
    (net (code "68") (name "Net-(OLED7-C2P)") (class "Default")
      (node (ref "C43") (pin "1") (pinfunction "1_1") (pintype "passive"))
      (node (ref "OLED7") (pin "2") (pinfunction "C2P_2") (pintype "bidirectional"))
    )
    (net (code "69") (name "Net-(OLED7-IREF)") (class "Default")
      (node (ref "OLED7") (pin "24") (pinfunction "IREF_24") (pintype "bidirectional"))
      (node (ref "R9") (pin "1") (pinfunction "1_1") (pintype "passive"))
    )
    (net (code "70") (name "Net-(OLED7-VCC)") (class "Default")
      (node (ref "C42") (pin "1") (pinfunction "1_1") (pintype "passive"))
      (node (ref "OLED7") (pin "26") (pinfunction "VCC_26") (pintype "bidirectional"))
    )
    (net (code "71") (name "Net-(OLED7-VCOMH)") (class "Default")
      (node (ref "C41") (pin "1") (pinfunction "1_1") (pintype "passive"))
      (node (ref "OLED7") (pin "25") (pinfunction "VCOMH_25") (pintype "bidirectional"))
    )
    (net (code "72") (name "Net-(OLED8-C1N)") (class "Default")
      (node (ref "C49") (pin "2") (pinfunction "2_2") (pintype "passive"))
      (node (ref "OLED8") (pin "5") (pinfunction "C1N_5") (pintype "bidirectional"))
    )
    (net (code "73") (name "Net-(OLED8-C1P)") (class "Default")
      (node (ref "C49") (pin "1") (pinfunction "1_1") (pintype "passive"))
      (node (ref "OLED8") (pin "4") (pinfunction "C1P_4") (pintype "bidirectional"))
    )
    (net (code "74") (name "Net-(OLED8-C2N)") (class "Default")
      (node (ref "C48") (pin "2") (pinfunction "2_2") (pintype "passive"))
      (node (ref "OLED8") (pin "3") (pinfunction "C2N_3") (pintype "bidirectional"))
    )
    (net (code "75") (name "Net-(OLED8-C2P)") (class "Default")
      (node (ref "C48") (pin "1") (pinfunction "1_1") (pintype "passive"))
      (node (ref "OLED8") (pin "2") (pinfunction "C2P_2") (pintype "bidirectional"))
    )
    (net (code "76") (name "Net-(OLED8-IREF)") (class "Default")
      (node (ref "OLED8") (pin "24") (pinfunction "IREF_24") (pintype "bidirectional"))
      (node (ref "R10") (pin "1") (pinfunction "1_1") (pintype "passive"))
    )
    (net (code "77") (name "Net-(OLED8-VCC)") (class "Default")
      (node (ref "C47") (pin "1") (pinfunction "1_1") (pintype "passive"))
      (node (ref "OLED8") (pin "26") (pinfunction "VCC_26") (pintype "bidirectional"))
    )
    (net (code "78") (name "Net-(OLED8-VCOMH)") (class "Default")
      (node (ref "C46") (pin "1") (pinfunction "1_1") (pintype "passive"))
      (node (ref "OLED8") (pin "25") (pinfunction "VCOMH_25") (pintype "bidirectional"))
    )
    (net (code "79") (name "Net-(OLED9-C1N)") (class "Default")
      (node (ref "C54") (pin "2") (pinfunction "2_2") (pintype "passive"))
      (node (ref "OLED9") (pin "5") (pinfunction "C1N_5") (pintype "bidirectional"))
    )
    (net (code "80") (name "Net-(OLED9-C1P)") (class "Default")
      (node (ref "C54") (pin "1") (pinfunction "1_1") (pintype "passive"))
      (node (ref "OLED9") (pin "4") (pinfunction "C1P_4") (pintype "bidirectional"))
    )
    (net (code "81") (name "Net-(OLED9-C2N)") (class "Default")
      (node (ref "C53") (pin "2") (pinfunction "2_2") (pintype "passive"))
      (node (ref "OLED9") (pin "3") (pinfunction "C2N_3") (pintype "bidirectional"))
    )
    (net (code "82") (name "Net-(OLED9-C2P)") (class "Default")
      (node (ref "C53") (pin "1") (pinfunction "1_1") (pintype "passive"))
      (node (ref "OLED9") (pin "2") (pinfunction "C2P_2") (pintype "bidirectional"))
    )
    (net (code "83") (name "Net-(OLED9-IREF)") (class "Default")
      (node (ref "OLED9") (pin "24") (pinfunction "IREF_24") (pintype "bidirectional"))
      (node (ref "R11") (pin "1") (pinfunction "1_1") (pintype "passive"))
    )
    (net (code "84") (name "Net-(OLED9-VCC)") (class "Default")
      (node (ref "C52") (pin "1") (pinfunction "1_1") (pintype "passive"))
      (node (ref "OLED9") (pin "26") (pinfunction "VCC_26") (pintype "bidirectional"))
    )
    (net (code "85") (name "Net-(OLED9-VCOMH)") (class "Default")
      (node (ref "C51") (pin "1") (pinfunction "1_1") (pintype "passive"))
      (node (ref "OLED9") (pin "25") (pinfunction "VCOMH_25") (pintype "bidirectional"))
    )
    (net (code "86") (name "Net-(R17-Pad1)") (class "Default")
      (node (ref "R17") (pin "1") (pinfunction "1_1") (pintype "passive"))
      (node (ref "SJ1") (pin "2") (pinfunction "2_2") (pintype "passive"))
    )
    (net (code "87") (name "Net-(R18-Pad1)") (class "Default")
      (node (ref "R18") (pin "1") (pinfunction "1_1") (pintype "passive"))
      (node (ref "SJ2") (pin "2") (pinfunction "2_2") (pintype "passive"))
    )
    (net (code "88") (name "Net-(SW10-S)") (class "Default")
      (node (ref "R16") (pin "2") (pinfunction "2_2") (pintype "passive"))
      (node (ref "SW10") (pin "B") (pinfunction "S_B") (pintype "passive"))
      (node (ref "SW10") (pin "B'") (pinfunction "S1_B'") (pintype "passive"))
    )
    (net (code "89") (name "OSC_IN") (class "Default")
      (node (ref "C6") (pin "2") (pinfunction "2_2") (pintype "passive"))
      (node (ref "OSC") (pin "1") (pinfunction "1_1") (pintype "passive"))
      (node (ref "UC1") (pin "5") (pinfunction "PD0-OSC_IN_5") (pintype "input"))
    )
    (net (code "90") (name "OSC_OUT") (class "Default")
      (node (ref "C7") (pin "2") (pinfunction "2_2") (pintype "passive"))
      (node (ref "OSC") (pin "3") (pinfunction "2_3") (pintype "passive"))
      (node (ref "UC1") (pin "6") (pinfunction "PD1-OSC_OUT_6") (pintype "input"))
    )
    (net (code "91") (name "RESET") (class "Default")
      (node (ref "R8") (pin "1") (pinfunction "1_1") (pintype "passive"))
      (node (ref "SW10") (pin "A") (pinfunction "P_A") (pintype "passive"))
      (node (ref "SW10") (pin "A'") (pinfunction "P1_A'") (pintype "passive"))
      (node (ref "UC1") (pin "7") (pinfunction "NRST_7") (pintype "input"))
    )
    (net (code "92") (name "SCK") (class "Default")
      (node (ref "OLED1") (pin "16") (pinfunction "D0/SCK_16") (pintype "bidirectional"))
      (node (ref "OLED2") (pin "16") (pinfunction "D0/SCK_16") (pintype "bidirectional"))
      (node (ref "OLED3") (pin "16") (pinfunction "D0/SCK_16") (pintype "bidirectional"))
      (node (ref "OLED4") (pin "16") (pinfunction "D0/SCK_16") (pintype "bidirectional"))
      (node (ref "OLED5") (pin "16") (pinfunction "D0/SCK_16") (pintype "bidirectional"))
      (node (ref "OLED6") (pin "16") (pinfunction "D0/SCK_16") (pintype "bidirectional"))
      (node (ref "OLED7") (pin "16") (pinfunction "D0/SCK_16") (pintype "bidirectional"))
      (node (ref "OLED8") (pin "16") (pinfunction "D0/SCK_16") (pintype "bidirectional"))
      (node (ref "OLED9") (pin "16") (pinfunction "D0/SCK_16") (pintype "bidirectional"))
      (node (ref "UC1") (pin "15") (pinfunction "PA5/SPI1_SCK/ADC12_IN5_15") (pintype "bidirectional"))
    )
    (net (code "93") (name "SW01") (class "Default")
      (node (ref "SW1") (pin "A") (pinfunction "P_A") (pintype "passive"))
      (node (ref "SW1") (pin "A'") (pinfunction "P1_A'") (pintype "passive"))
      (node (ref "UC1") (pin "13") (pinfunction "PA3/USART2_RX/ADC12_IN3/TIM2_CH4_13") (pintype "bidirectional"))
    )
    (net (code "94") (name "SW02") (class "Default")
      (node (ref "SW2") (pin "A") (pinfunction "P_A") (pintype "passive"))
      (node (ref "UC1") (pin "18") (pinfunction "PB0/ADC12_IN8/TIM3_CH3_18") (pintype "bidirectional"))
    )
    (net (code "95") (name "SW03") (class "Default")
      (node (ref "SW3") (pin "A") (pinfunction "P_A") (pintype "passive"))
      (node (ref "SW3") (pin "A'") (pinfunction "P1_A'") (pintype "passive"))
      (node (ref "UC1") (pin "25") (pinfunction "PB12/SPI2_NSS/I2C2_SMBA/USART3_CK/TIM1_BKIN_25") (pintype "input"))
    )
    (net (code "96") (name "SW04") (class "Default")
      (node (ref "SW4") (pin "A") (pinfunction "P_A") (pintype "passive"))
      (node (ref "SW4") (pin "A'") (pinfunction "P1_A'") (pintype "passive"))
      (node (ref "UC1") (pin "38") (pinfunction "PA15/JTDI_38") (pintype "bidirectional"))
    )
    (net (code "97") (name "SW05") (class "Default")
      (node (ref "SW5") (pin "A") (pinfunction "P_A") (pintype "passive"))
      (node (ref "SW5") (pin "A'") (pinfunction "P1_A'") (pintype "passive"))
      (node (ref "UC1") (pin "22") (pinfunction "PB11/I2C2_SDA/USART3_RX_22") (pintype "input"))
    )
    (net (code "98") (name "SW06") (class "Default")
      (node (ref "SW6") (pin "A") (pinfunction "P_A") (pintype "passive"))
      (node (ref "SW6") (pin "A'") (pinfunction "P1_A'") (pintype "passive"))
      (node (ref "UC1") (pin "30") (pinfunction "PA9/USART1_TX/TIM1_CH2_30") (pintype "input"))
    )
    (net (code "99") (name "SW07") (class "Default")
      (node (ref "SW7") (pin "A") (pinfunction "P_A") (pintype "passive"))
      (node (ref "SW7") (pin "A'") (pinfunction "P1_A'") (pintype "passive"))
      (node (ref "UC1") (pin "37") (pinfunction "PA14/JTCK/SWCLK_37") (pintype "bidirectional"))
    )
    (net (code "100") (name "SW08") (class "Default")
      (node (ref "SW8") (pin "A") (pinfunction "P_A") (pintype "passive"))
      (node (ref "SW8") (pin "A'") (pinfunction "P1_A'") (pintype "passive"))
      (node (ref "UC1") (pin "21") (pinfunction "PB10/I2C2_SCL/USART3_TX_21") (pintype "input"))
    )
    (net (code "101") (name "SW09") (class "Default")
      (node (ref "SW9") (pin "A") (pinfunction "P_A") (pintype "passive"))
      (node (ref "SW9") (pin "A'") (pinfunction "P1_A'") (pintype "passive"))
      (node (ref "UC1") (pin "29") (pinfunction "PA8/USART1_CK/TIM1_CH1/MCO_29") (pintype "bidirectional"))
    )
    (net (code "102") (name "UART1_RX") (class "Default")
      (node (ref "UC1") (pin "31") (pinfunction "PA10/USART1_RX/TIM1_CH3_31") (pintype "bidirectional"))
    )
    (net (code "103") (name "USBDM") (class "Default")
      (node (ref "C12") (pin "1") (pinfunction "1_1") (pintype "passive"))
      (node (ref "R14") (pin "2") (pinfunction "2_2") (pintype "passive"))
      (node (ref "UC1") (pin "32") (pinfunction "PA11/USART1_CTS/CAN_RX/TIM1_CH4/USBDM_32") (pintype "bidirectional"))
    )
    (net (code "104") (name "USBDP") (class "Default")
      (node (ref "C13") (pin "1") (pinfunction "1_1") (pintype "passive"))
      (node (ref "R13") (pin "2") (pinfunction "2_2") (pintype "passive"))
      (node (ref "R20") (pin "1") (pinfunction "1_1") (pintype "passive"))
      (node (ref "UC1") (pin "33") (pinfunction "PA12/USART1_RTS/CAN_TX/TIM1_ETR/USBDP_33") (pintype "bidirectional"))
    )
    (net (code "105") (name "V_USB") (class "Default")
      (node (ref "C8") (pin "1") (pinfunction "1_1") (pintype "passive"))
      (node (ref "F1") (pin "2") (pinfunction "2_2") (pintype "bidirectional"))
      (node (ref "U3") (pin "1") (pinfunction "IN_1") (pintype "input"))
      (node (ref "U3") (pin "3") (pinfunction "EN_3") (pintype "input"))
    )
    (net (code "106") (name "unconnected-(OLED1-D2-Pad18)") (class "Default")
      (node (ref "OLED1") (pin "18") (pinfunction "D2_18") (pintype "bidirectional"))
    )
    (net (code "107") (name "unconnected-(OLED1-D3-Pad19)") (class "Default")
      (node (ref "OLED1") (pin "19") (pinfunction "D3_19") (pintype "bidirectional"))
    )
    (net (code "108") (name "unconnected-(OLED1-D4-Pad20)") (class "Default")
      (node (ref "OLED1") (pin "20") (pinfunction "D4_20") (pintype "bidirectional"))
    )
    (net (code "109") (name "unconnected-(OLED1-D5-Pad21)") (class "Default")
      (node (ref "OLED1") (pin "21") (pinfunction "D5_21") (pintype "bidirectional"))
    )
    (net (code "110") (name "unconnected-(OLED1-D6-Pad22)") (class "Default")
      (node (ref "OLED1") (pin "22") (pinfunction "D6_22") (pintype "bidirectional"))
    )
    (net (code "111") (name "unconnected-(OLED1-D7-Pad23)") (class "Default")
      (node (ref "OLED1") (pin "23") (pinfunction "D7_23") (pintype "bidirectional"))
    )
    (net (code "112") (name "unconnected-(OLED1-E{slash}~{RD}-Pad15)") (class "Default")
      (node (ref "OLED1") (pin "15") (pinfunction "E/~{RD}_15") (pintype "bidirectional"))
    )
    (net (code "113") (name "unconnected-(OLED1-R{slash}~{W}-Pad14)") (class "Default")
      (node (ref "OLED1") (pin "14") (pinfunction "R/~{W}_14") (pintype "bidirectional"))
    )
    (net (code "114") (name "unconnected-(OLED2-D2-Pad18)") (class "Default")
      (node (ref "OLED2") (pin "18") (pinfunction "D2_18") (pintype "bidirectional"))
    )
    (net (code "115") (name "unconnected-(OLED2-D3-Pad19)") (class "Default")
      (node (ref "OLED2") (pin "19") (pinfunction "D3_19") (pintype "bidirectional"))
    )
    (net (code "116") (name "unconnected-(OLED2-D4-Pad20)") (class "Default")
      (node (ref "OLED2") (pin "20") (pinfunction "D4_20") (pintype "bidirectional"))
    )
    (net (code "117") (name "unconnected-(OLED2-D5-Pad21)") (class "Default")
      (node (ref "OLED2") (pin "21") (pinfunction "D5_21") (pintype "bidirectional"))
    )
    (net (code "118") (name "unconnected-(OLED2-D6-Pad22)") (class "Default")
      (node (ref "OLED2") (pin "22") (pinfunction "D6_22") (pintype "bidirectional"))
    )
    (net (code "119") (name "unconnected-(OLED2-D7-Pad23)") (class "Default")
      (node (ref "OLED2") (pin "23") (pinfunction "D7_23") (pintype "bidirectional"))
    )
    (net (code "120") (name "unconnected-(OLED2-E{slash}~{RD}-Pad15)") (class "Default")
      (node (ref "OLED2") (pin "15") (pinfunction "E/~{RD}_15") (pintype "bidirectional"))
    )
    (net (code "121") (name "unconnected-(OLED2-R{slash}~{W}-Pad14)") (class "Default")
      (node (ref "OLED2") (pin "14") (pinfunction "R/~{W}_14") (pintype "bidirectional"))
    )
    (net (code "122") (name "unconnected-(OLED3-D2-Pad18)") (class "Default")
      (node (ref "OLED3") (pin "18") (pinfunction "D2_18") (pintype "bidirectional"))
    )
    (net (code "123") (name "unconnected-(OLED3-D3-Pad19)") (class "Default")
      (node (ref "OLED3") (pin "19") (pinfunction "D3_19") (pintype "bidirectional"))
    )
    (net (code "124") (name "unconnected-(OLED3-D4-Pad20)") (class "Default")
      (node (ref "OLED3") (pin "20") (pinfunction "D4_20") (pintype "bidirectional"))
    )
    (net (code "125") (name "unconnected-(OLED3-D5-Pad21)") (class "Default")
      (node (ref "OLED3") (pin "21") (pinfunction "D5_21") (pintype "bidirectional"))
    )
    (net (code "126") (name "unconnected-(OLED3-D6-Pad22)") (class "Default")
      (node (ref "OLED3") (pin "22") (pinfunction "D6_22") (pintype "bidirectional"))
    )
    (net (code "127") (name "unconnected-(OLED3-D7-Pad23)") (class "Default")
      (node (ref "OLED3") (pin "23") (pinfunction "D7_23") (pintype "bidirectional"))
    )
    (net (code "128") (name "unconnected-(OLED3-E{slash}~{RD}-Pad15)") (class "Default")
      (node (ref "OLED3") (pin "15") (pinfunction "E/~{RD}_15") (pintype "bidirectional"))
    )
    (net (code "129") (name "unconnected-(OLED3-R{slash}~{W}-Pad14)") (class "Default")
      (node (ref "OLED3") (pin "14") (pinfunction "R/~{W}_14") (pintype "bidirectional"))
    )
    (net (code "130") (name "unconnected-(OLED4-D2-Pad18)") (class "Default")
      (node (ref "OLED4") (pin "18") (pinfunction "D2_18") (pintype "bidirectional"))
    )
    (net (code "131") (name "unconnected-(OLED4-D3-Pad19)") (class "Default")
      (node (ref "OLED4") (pin "19") (pinfunction "D3_19") (pintype "bidirectional"))
    )
    (net (code "132") (name "unconnected-(OLED4-D4-Pad20)") (class "Default")
      (node (ref "OLED4") (pin "20") (pinfunction "D4_20") (pintype "bidirectional"))
    )
    (net (code "133") (name "unconnected-(OLED4-D5-Pad21)") (class "Default")
      (node (ref "OLED4") (pin "21") (pinfunction "D5_21") (pintype "bidirectional"))
    )
    (net (code "134") (name "unconnected-(OLED4-D6-Pad22)") (class "Default")
      (node (ref "OLED4") (pin "22") (pinfunction "D6_22") (pintype "bidirectional"))
    )
    (net (code "135") (name "unconnected-(OLED4-D7-Pad23)") (class "Default")
      (node (ref "OLED4") (pin "23") (pinfunction "D7_23") (pintype "bidirectional"))
    )
    (net (code "136") (name "unconnected-(OLED4-E{slash}~{RD}-Pad15)") (class "Default")
      (node (ref "OLED4") (pin "15") (pinfunction "E/~{RD}_15") (pintype "bidirectional"))
    )
    (net (code "137") (name "unconnected-(OLED4-R{slash}~{W}-Pad14)") (class "Default")
      (node (ref "OLED4") (pin "14") (pinfunction "R/~{W}_14") (pintype "bidirectional"))
    )
    (net (code "138") (name "unconnected-(OLED5-D2-Pad18)") (class "Default")
      (node (ref "OLED5") (pin "18") (pinfunction "D2_18") (pintype "bidirectional"))
    )
    (net (code "139") (name "unconnected-(OLED5-D3-Pad19)") (class "Default")
      (node (ref "OLED5") (pin "19") (pinfunction "D3_19") (pintype "bidirectional"))
    )
    (net (code "140") (name "unconnected-(OLED5-D4-Pad20)") (class "Default")
      (node (ref "OLED5") (pin "20") (pinfunction "D4_20") (pintype "bidirectional"))
    )
    (net (code "141") (name "unconnected-(OLED5-D5-Pad21)") (class "Default")
      (node (ref "OLED5") (pin "21") (pinfunction "D5_21") (pintype "bidirectional"))
    )
    (net (code "142") (name "unconnected-(OLED5-D6-Pad22)") (class "Default")
      (node (ref "OLED5") (pin "22") (pinfunction "D6_22") (pintype "bidirectional"))
    )
    (net (code "143") (name "unconnected-(OLED5-D7-Pad23)") (class "Default")
      (node (ref "OLED5") (pin "23") (pinfunction "D7_23") (pintype "bidirectional"))
    )
    (net (code "144") (name "unconnected-(OLED5-E{slash}~{RD}-Pad15)") (class "Default")
      (node (ref "OLED5") (pin "15") (pinfunction "E/~{RD}_15") (pintype "bidirectional"))
    )
    (net (code "145") (name "unconnected-(OLED5-R{slash}~{W}-Pad14)") (class "Default")
      (node (ref "OLED5") (pin "14") (pinfunction "R/~{W}_14") (pintype "bidirectional"))
    )
    (net (code "146") (name "unconnected-(OLED6-D2-Pad18)") (class "Default")
      (node (ref "OLED6") (pin "18") (pinfunction "D2_18") (pintype "bidirectional"))
    )
    (net (code "147") (name "unconnected-(OLED6-D3-Pad19)") (class "Default")
      (node (ref "OLED6") (pin "19") (pinfunction "D3_19") (pintype "bidirectional"))
    )
    (net (code "148") (name "unconnected-(OLED6-D4-Pad20)") (class "Default")
      (node (ref "OLED6") (pin "20") (pinfunction "D4_20") (pintype "bidirectional"))
    )
    (net (code "149") (name "unconnected-(OLED6-D5-Pad21)") (class "Default")
      (node (ref "OLED6") (pin "21") (pinfunction "D5_21") (pintype "bidirectional"))
    )
    (net (code "150") (name "unconnected-(OLED6-D6-Pad22)") (class "Default")
      (node (ref "OLED6") (pin "22") (pinfunction "D6_22") (pintype "bidirectional"))
    )
    (net (code "151") (name "unconnected-(OLED6-D7-Pad23)") (class "Default")
      (node (ref "OLED6") (pin "23") (pinfunction "D7_23") (pintype "bidirectional"))
    )
    (net (code "152") (name "unconnected-(OLED6-E{slash}~{RD}-Pad15)") (class "Default")
      (node (ref "OLED6") (pin "15") (pinfunction "E/~{RD}_15") (pintype "bidirectional"))
    )
    (net (code "153") (name "unconnected-(OLED6-R{slash}~{W}-Pad14)") (class "Default")
      (node (ref "OLED6") (pin "14") (pinfunction "R/~{W}_14") (pintype "bidirectional"))
    )
    (net (code "154") (name "unconnected-(OLED7-D2-Pad18)") (class "Default")
      (node (ref "OLED7") (pin "18") (pinfunction "D2_18") (pintype "bidirectional"))
    )
    (net (code "155") (name "unconnected-(OLED7-D3-Pad19)") (class "Default")
      (node (ref "OLED7") (pin "19") (pinfunction "D3_19") (pintype "bidirectional"))
    )
    (net (code "156") (name "unconnected-(OLED7-D4-Pad20)") (class "Default")
      (node (ref "OLED7") (pin "20") (pinfunction "D4_20") (pintype "bidirectional"))
    )
    (net (code "157") (name "unconnected-(OLED7-D5-Pad21)") (class "Default")
      (node (ref "OLED7") (pin "21") (pinfunction "D5_21") (pintype "bidirectional"))
    )
    (net (code "158") (name "unconnected-(OLED7-D6-Pad22)") (class "Default")
      (node (ref "OLED7") (pin "22") (pinfunction "D6_22") (pintype "bidirectional"))
    )
    (net (code "159") (name "unconnected-(OLED7-D7-Pad23)") (class "Default")
      (node (ref "OLED7") (pin "23") (pinfunction "D7_23") (pintype "bidirectional"))
    )
    (net (code "160") (name "unconnected-(OLED7-E{slash}~{RD}-Pad15)") (class "Default")
      (node (ref "OLED7") (pin "15") (pinfunction "E/~{RD}_15") (pintype "bidirectional"))
    )
    (net (code "161") (name "unconnected-(OLED7-R{slash}~{W}-Pad14)") (class "Default")
      (node (ref "OLED7") (pin "14") (pinfunction "R/~{W}_14") (pintype "bidirectional"))
    )
    (net (code "162") (name "unconnected-(OLED8-D2-Pad18)") (class "Default")
      (node (ref "OLED8") (pin "18") (pinfunction "D2_18") (pintype "bidirectional"))
    )
    (net (code "163") (name "unconnected-(OLED8-D3-Pad19)") (class "Default")
      (node (ref "OLED8") (pin "19") (pinfunction "D3_19") (pintype "bidirectional"))
    )
    (net (code "164") (name "unconnected-(OLED8-D4-Pad20)") (class "Default")
      (node (ref "OLED8") (pin "20") (pinfunction "D4_20") (pintype "bidirectional"))
    )
    (net (code "165") (name "unconnected-(OLED8-D5-Pad21)") (class "Default")
      (node (ref "OLED8") (pin "21") (pinfunction "D5_21") (pintype "bidirectional"))
    )
    (net (code "166") (name "unconnected-(OLED8-D6-Pad22)") (class "Default")
      (node (ref "OLED8") (pin "22") (pinfunction "D6_22") (pintype "bidirectional"))
    )
    (net (code "167") (name "unconnected-(OLED8-D7-Pad23)") (class "Default")
      (node (ref "OLED8") (pin "23") (pinfunction "D7_23") (pintype "bidirectional"))
    )
    (net (code "168") (name "unconnected-(OLED8-E{slash}~{RD}-Pad15)") (class "Default")
      (node (ref "OLED8") (pin "15") (pinfunction "E/~{RD}_15") (pintype "bidirectional"))
    )
    (net (code "169") (name "unconnected-(OLED8-R{slash}~{W}-Pad14)") (class "Default")
      (node (ref "OLED8") (pin "14") (pinfunction "R/~{W}_14") (pintype "bidirectional"))
    )
    (net (code "170") (name "unconnected-(OLED9-D2-Pad18)") (class "Default")
      (node (ref "OLED9") (pin "18") (pinfunction "D2_18") (pintype "bidirectional"))
    )
    (net (code "171") (name "unconnected-(OLED9-D3-Pad19)") (class "Default")
      (node (ref "OLED9") (pin "19") (pinfunction "D3_19") (pintype "bidirectional"))
    )
    (net (code "172") (name "unconnected-(OLED9-D4-Pad20)") (class "Default")
      (node (ref "OLED9") (pin "20") (pinfunction "D4_20") (pintype "bidirectional"))
    )
    (net (code "173") (name "unconnected-(OLED9-D5-Pad21)") (class "Default")
      (node (ref "OLED9") (pin "21") (pinfunction "D5_21") (pintype "bidirectional"))
    )
    (net (code "174") (name "unconnected-(OLED9-D6-Pad22)") (class "Default")
      (node (ref "OLED9") (pin "22") (pinfunction "D6_22") (pintype "bidirectional"))
    )
    (net (code "175") (name "unconnected-(OLED9-D7-Pad23)") (class "Default")
      (node (ref "OLED9") (pin "23") (pinfunction "D7_23") (pintype "bidirectional"))
    )
    (net (code "176") (name "unconnected-(OLED9-E{slash}~{RD}-Pad15)") (class "Default")
      (node (ref "OLED9") (pin "15") (pinfunction "E/~{RD}_15") (pintype "bidirectional"))
    )
    (net (code "177") (name "unconnected-(OLED9-R{slash}~{W}-Pad14)") (class "Default")
      (node (ref "OLED9") (pin "14") (pinfunction "R/~{W}_14") (pintype "bidirectional"))
    )
    (net (code "178") (name "unconnected-(SW2-P1-PadA')") (class "Default")
      (node (ref "SW2") (pin "A'") (pinfunction "P1_A'") (pintype "passive"))
    )
    (net (code "179") (name "unconnected-(U3-BP-Pad4)") (class "Default")
      (node (ref "U3") (pin "4") (pinfunction "BP_4") (pintype "input"))
    )
    (net (code "180") (name "unconnected-(UC1-PA0_WKUP{slash}USART2_CTS{slash}ADC12_IN0{slash}TIM2_CH1_ETR-Pad10)") (class "Default")
      (node (ref "UC1") (pin "10") (pinfunction "PA0_WKUP/USART2_CTS/ADC12_IN0/TIM2_CH1_ETR_10") (pintype "bidirectional"))
    )
    (net (code "181") (name "unconnected-(UC1-PA13{slash}JTMS{slash}SWDIO-Pad34)") (class "Default")
      (node (ref "UC1") (pin "34") (pinfunction "PA13/JTMS/SWDIO_34") (pintype "bidirectional"))
    )
    (net (code "182") (name "unconnected-(UC1-PB6{slash}I2C1_SCL{slash}TIM4_CH1-Pad42)") (class "Default")
      (node (ref "UC1") (pin "42") (pinfunction "PB6/I2C1_SCL/TIM4_CH1_42") (pintype "input"))
    )
    (net (code "183") (name "unconnected-(UC1-PB7{slash}I2C1_SDA{slash}TIM4_CH2-Pad43)") (class "Default")
      (node (ref "UC1") (pin "43") (pinfunction "PB7/I2C1_SDA/TIM4_CH2_43") (pintype "bidirectional"))
    )
    (net (code "184") (name "unconnected-(UC1-PB8{slash}TIM4_CH3-Pad45)") (class "Default")
      (node (ref "UC1") (pin "45") (pinfunction "PB8/TIM4_CH3_45") (pintype "bidirectional"))
    )
    (net (code "185") (name "unconnected-(UC1-PB9{slash}TIM4_CH4-Pad46)") (class "Default")
      (node (ref "UC1") (pin "46") (pinfunction "PB9/TIM4_CH4_46") (pintype "input"))
    )
    (net (code "186") (name "unconnected-(UC1-PC13-TAMPER-RTC-Pad2)") (class "Default")
      (node (ref "UC1") (pin "2") (pinfunction "PC13-TAMPER-RTC_2") (pintype "input"))
    )
    (net (code "187") (name "unconnected-(UC1-PC14-OSC32_IN-Pad3)") (class "Default")
      (node (ref "UC1") (pin "3") (pinfunction "PC14-OSC32_IN_3") (pintype "input"))
    )
    (net (code "188") (name "unconnected-(UC1-PC15-OSC32_OUT-Pad4)") (class "Default")
      (node (ref "UC1") (pin "4") (pinfunction "PC15-OSC32_OUT_4") (pintype "input"))
    )
  )
)
